# polarTRX.net
KiCad netlist of a schematic drawn in EAGLE
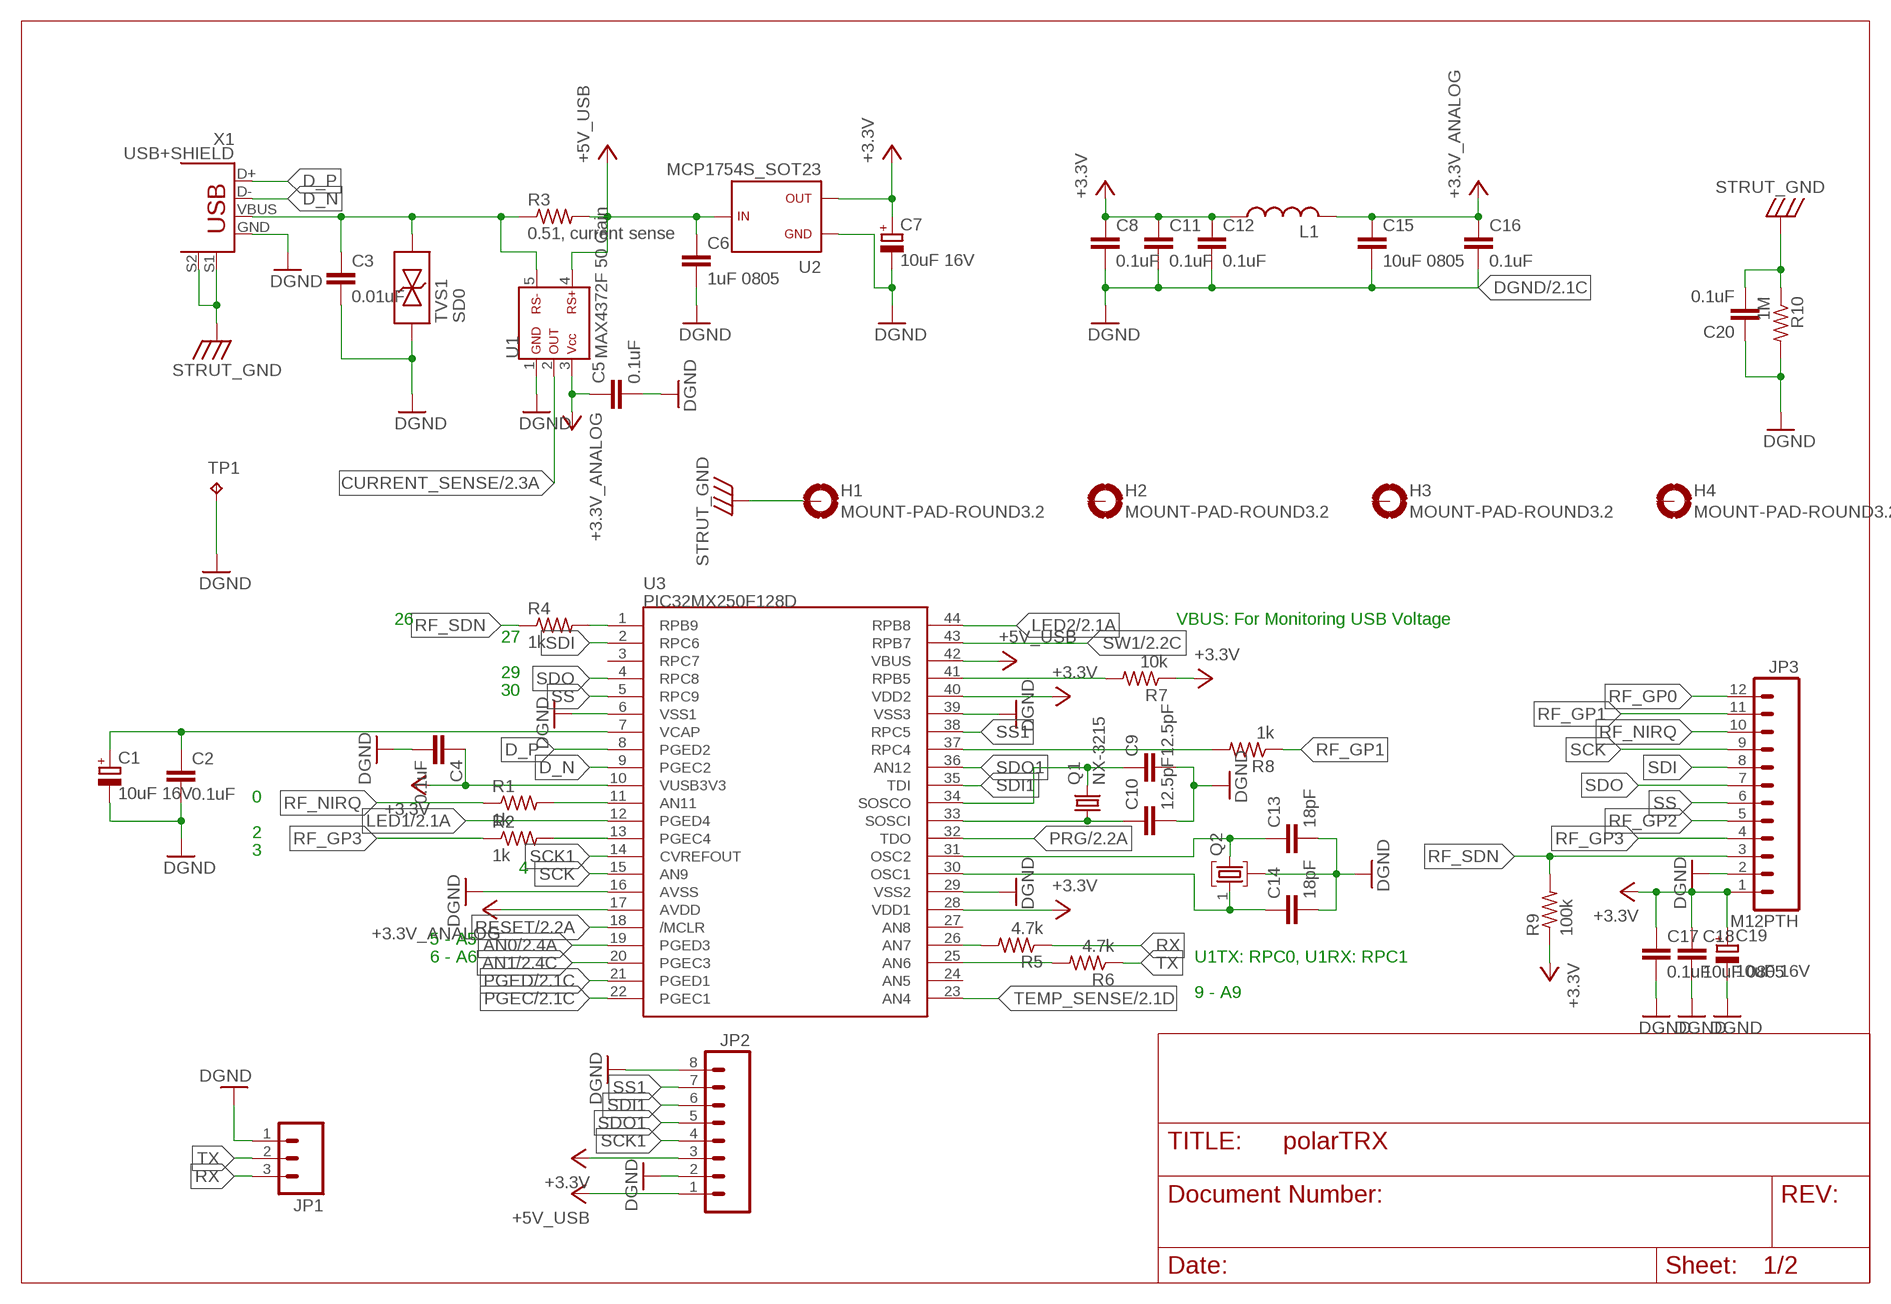
[diagram p0: schematic, sheet 1]
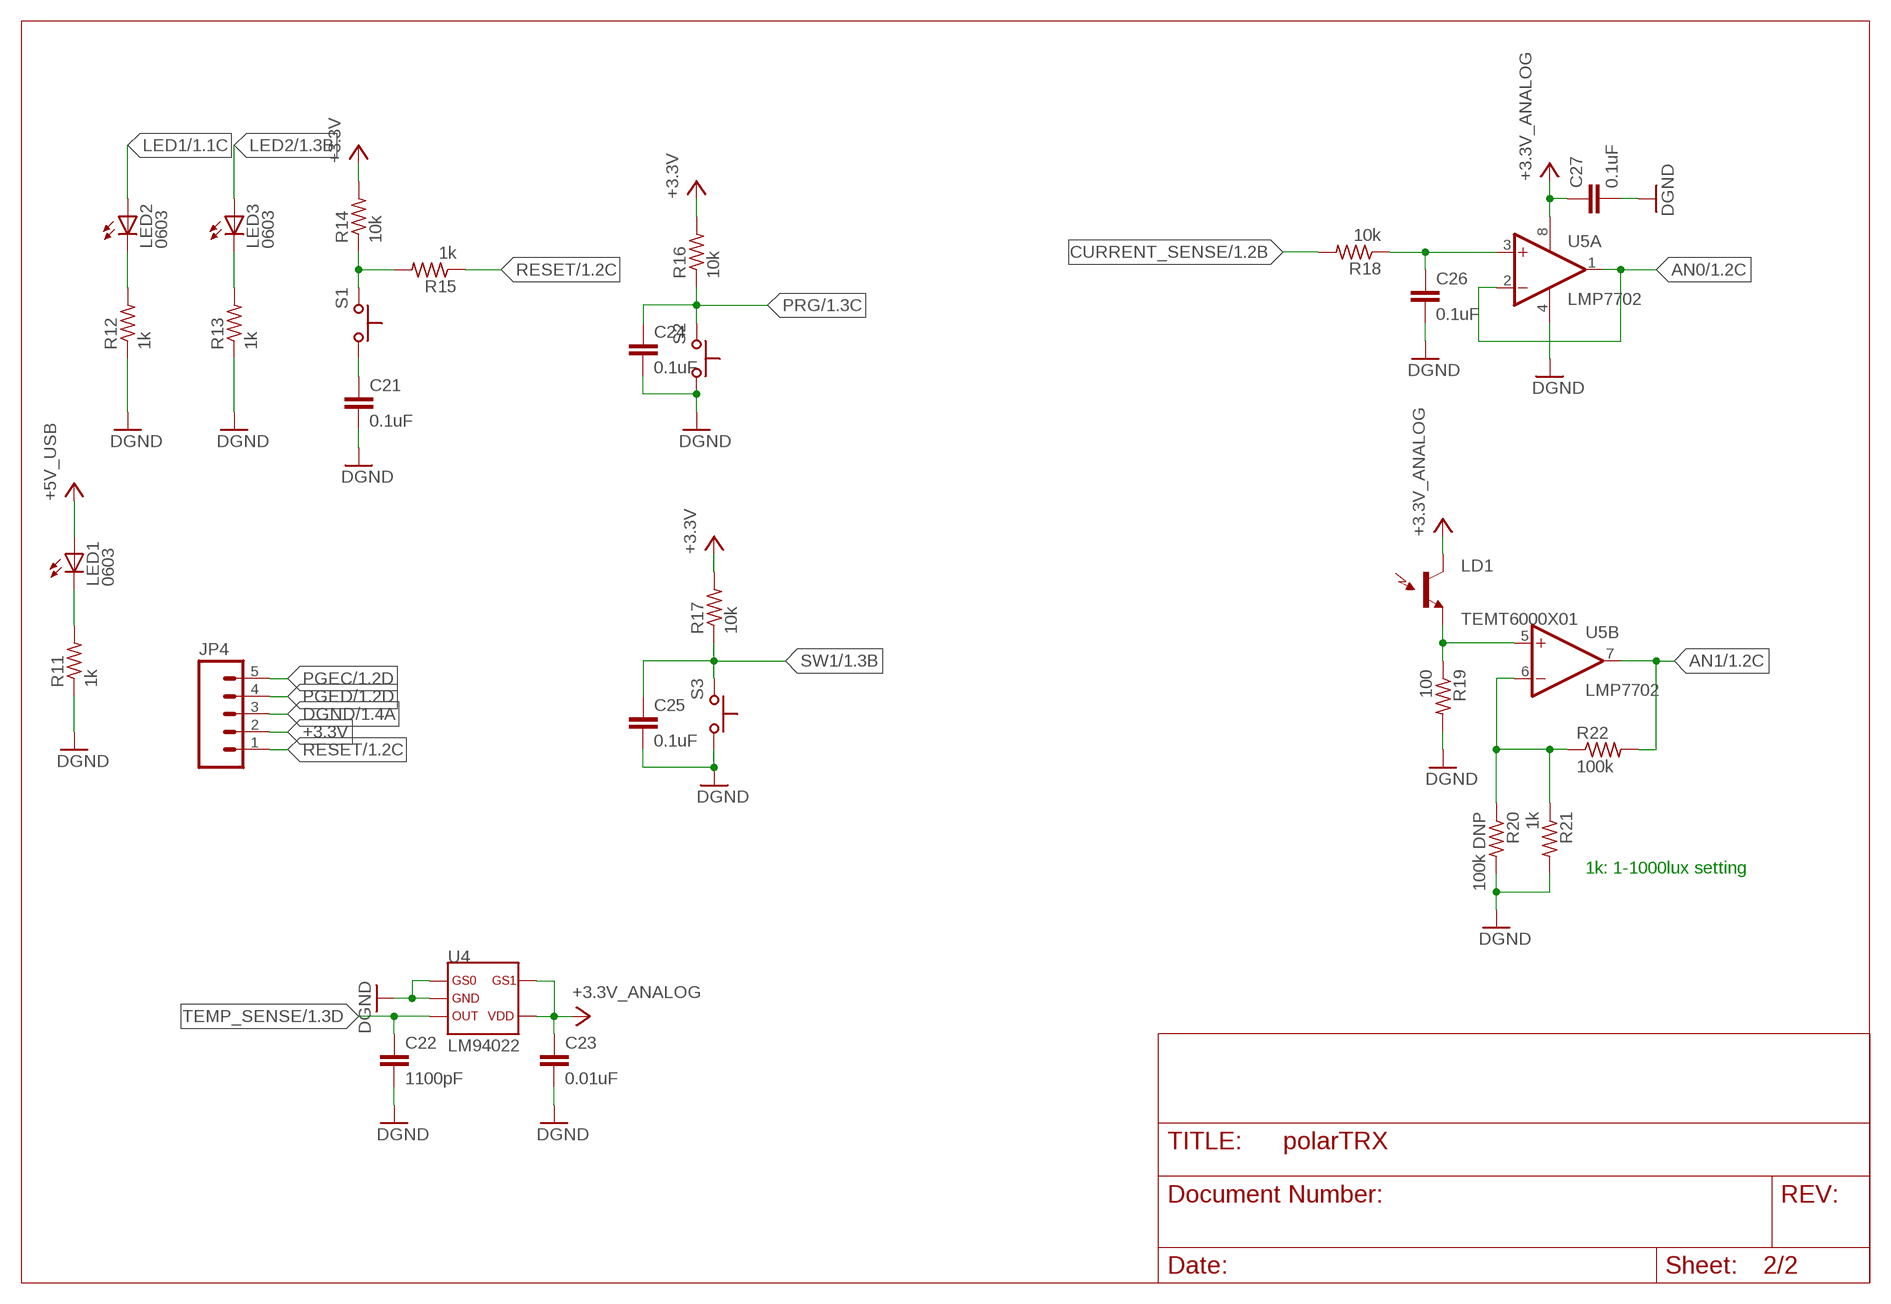
[diagram p1: schematic, sheet 2]

(export (version "E")
  (design (tool "Eeschema 10.0.6"))
  (components
    (comp (ref "C1")
      (value "10uF 16V")
      (footprint "eagle-import:C1206(3216)-A")
      (libsource (lib "eagle-import") (part "C-TANTAL-A"))
    )
    (comp (ref "C2")
      (value "0.1uF")
      (footprint "eagle-import:C0603(1608)")
      (libsource (lib "eagle-import") (part "C0603(1608)"))
    )
    (comp (ref "C3")
      (value "0.01uF")
      (footprint "eagle-import:C0603(1608)")
      (libsource (lib "eagle-import") (part "C0603(1608)"))
    )
    (comp (ref "C4")
      (value "0.1uF")
      (footprint "eagle-import:C0603(1608)")
      (libsource (lib "eagle-import") (part "C0603(1608)"))
    )
    (comp (ref "C5")
      (value "0.1uF")
      (footprint "eagle-import:C0603(1608)")
      (libsource (lib "eagle-import") (part "C0603(1608)"))
    )
    (comp (ref "C6")
      (value "1uF 0805")
      (footprint "eagle-import:C0805(2012)")
      (libsource (lib "eagle-import") (part "C0805(2012)"))
    )
    (comp (ref "C7")
      (value "10uF 16V")
      (footprint "eagle-import:C1206(3216)-A")
      (libsource (lib "eagle-import") (part "C-TANTAL-A"))
    )
    (comp (ref "C8")
      (value "0.1uF")
      (footprint "eagle-import:C0603(1608)")
      (libsource (lib "eagle-import") (part "C0603(1608)"))
    )
    (comp (ref "C9")
      (value "12.5pF")
      (footprint "eagle-import:C0603(1608)")
      (libsource (lib "eagle-import") (part "C0603(1608)"))
    )
    (comp (ref "C10")
      (value "12.5pF")
      (footprint "eagle-import:C0603(1608)")
      (libsource (lib "eagle-import") (part "C0603(1608)"))
    )
    (comp (ref "C11")
      (value "0.1uF")
      (footprint "eagle-import:C0603(1608)")
      (libsource (lib "eagle-import") (part "C0603(1608)"))
    )
    (comp (ref "C12")
      (value "0.1uF")
      (footprint "eagle-import:C0603(1608)")
      (libsource (lib "eagle-import") (part "C0603(1608)"))
    )
    (comp (ref "C13")
      (value "18pF")
      (footprint "eagle-import:C0603(1608)")
      (libsource (lib "eagle-import") (part "C0603(1608)"))
    )
    (comp (ref "C14")
      (value "18pF")
      (footprint "eagle-import:C0603(1608)")
      (libsource (lib "eagle-import") (part "C0603(1608)"))
    )
    (comp (ref "C15")
      (value "10uF 0805")
      (footprint "eagle-import:C0805(2012)")
      (libsource (lib "eagle-import") (part "C0805(2012)"))
    )
    (comp (ref "C16")
      (value "0.1uF")
      (footprint "eagle-import:C0603(1608)")
      (libsource (lib "eagle-import") (part "C0603(1608)"))
    )
    (comp (ref "C17")
      (value "0.1uF")
      (footprint "eagle-import:C0603(1608)")
      (libsource (lib "eagle-import") (part "C0603(1608)"))
    )
    (comp (ref "C18")
      (value "10uF 0805")
      (footprint "eagle-import:C0805(2012)")
      (libsource (lib "eagle-import") (part "C0805(2012)"))
    )
    (comp (ref "C19")
      (value "10uF 16V")
      (footprint "eagle-import:C1206(3216)-A")
      (libsource (lib "eagle-import") (part "C-TANTAL-A"))
    )
    (comp (ref "C20")
      (value "0.1uF")
      (footprint "eagle-import:C0603(1608)")
      (libsource (lib "eagle-import") (part "yBrainDigital_C0603(1608)"))
    )
    (comp (ref "H1")
      (value "MOUNT-PAD-ROUND3.2")
      (footprint "eagle-import:3,2-PAD")
      (libsource (lib "eagle-import") (part "MOUNT-PAD-ROUND3.2"))
    )
    (comp (ref "H2")
      (value "MOUNT-PAD-ROUND3.2")
      (footprint "eagle-import:3,2-PAD")
      (libsource (lib "eagle-import") (part "MOUNT-PAD-ROUND3.2"))
    )
    (comp (ref "H3")
      (value "MOUNT-PAD-ROUND3.2")
      (footprint "eagle-import:3,2-PAD")
      (libsource (lib "eagle-import") (part "MOUNT-PAD-ROUND3.2"))
    )
    (comp (ref "H4")
      (value "MOUNT-PAD-ROUND3.2")
      (footprint "eagle-import:3,2-PAD")
      (libsource (lib "eagle-import") (part "MOUNT-PAD-ROUND3.2"))
    )
    (comp (ref "JP1")
      (value "M03PTH")
      (footprint "eagle-import:1X03")
      (libsource (lib "eagle-import") (part "M03PTH"))
    )
    (comp (ref "JP2")
      (value "M08SILK_FEMALE_PTH")
      (footprint "eagle-import:1X08")
      (libsource (lib "eagle-import") (part "M08SILK_FEMALE_PTH"))
    )
    (comp (ref "JP3")
      (value "M12PTH")
      (footprint "eagle-import:1X12")
      (libsource (lib "eagle-import") (part "M12PTH"))
    )
    (comp (ref "L1")
      (value "L0805(2012)")
      (footprint "eagle-import:L0805(2012)")
      (libsource (lib "eagle-import") (part "L0805(2012)"))
    )
    (comp (ref "Q1")
      (value "NX-3215")
      (footprint "eagle-import:NX-3215")
      (libsource (lib "eagle-import") (part "NX-3215"))
    )
    (comp (ref "Q2")
      (value "CRYSTAL")
      (footprint "eagle-import:HC_49US")
      (libsource (lib "eagle-import") (part "CRYSTAL"))
    )
    (comp (ref "R1")
      (value "1k")
      (footprint "eagle-import:R0603(1608)")
      (libsource (lib "eagle-import") (part "R0603(1608)"))
    )
    (comp (ref "R2")
      (value "1k")
      (footprint "eagle-import:R0603(1608)")
      (libsource (lib "eagle-import") (part "R0603(1608)"))
    )
    (comp (ref "R3")
      (value "0.51, current sense")
      (footprint "eagle-import:R0805(2012)")
      (libsource (lib "eagle-import") (part "R0805(2012)"))
    )
    (comp (ref "R4")
      (value "1k")
      (footprint "eagle-import:R0603(1608)")
      (libsource (lib "eagle-import") (part "R0603(1608)"))
    )
    (comp (ref "R5")
      (value "4.7k")
      (footprint "eagle-import:R0603(1608)")
      (libsource (lib "eagle-import") (part "R0603(1608)"))
    )
    (comp (ref "R6")
      (value "4.7k")
      (footprint "eagle-import:R0603(1608)")
      (libsource (lib "eagle-import") (part "R0603(1608)"))
    )
    (comp (ref "R7")
      (value "10k")
      (footprint "eagle-import:R0603(1608)")
      (libsource (lib "eagle-import") (part "R0603(1608)"))
    )
    (comp (ref "R8")
      (value "1k")
      (footprint "eagle-import:R0603(1608)")
      (libsource (lib "eagle-import") (part "R0603(1608)"))
    )
    (comp (ref "R9")
      (value "100k")
      (footprint "eagle-import:R0603(1608)")
      (libsource (lib "eagle-import") (part "R0603(1608)"))
    )
    (comp (ref "R10")
      (value "1M")
      (footprint "eagle-import:R0603(1608)")
      (libsource (lib "eagle-import") (part "yBrainDigital_R0603(1608)"))
    )
    (comp (ref "TP1")
      (value "TP")
      (footprint "eagle-import:TP-13")
      (libsource (lib "eagle-import") (part "TP"))
    )
    (comp (ref "TVS1")
      (value "SD0")
      (footprint "eagle-import:SOD-323-NOPOL")
      (libsource (lib "eagle-import") (part "SD0"))
    )
    (comp (ref "U1")
      (value "MAX4372F 50 Gain")
      (footprint "eagle-import:SOT23-5DBV")
      (libsource (lib "eagle-import") (part "MAX4372"))
    )
    (comp (ref "U2")
      (value "MCP1754S_SOT23")
      (footprint "eagle-import:SOT23")
      (libsource (lib "eagle-import") (part "MCP1754S_SOT23"))
    )
    (comp (ref "U3")
      (value "PIC32MX250F128D")
      (footprint "eagle-import:TQFP44")
      (libsource (lib "eagle-import") (part "PIC32MX250F128D"))
    )
    (comp (ref "X1")
      (value "USB+SHIELD")
      (footprint "eagle-import:USB-B-PTH")
      (libsource (lib "eagle-import") (part "USB+SHIELD"))
    )
    (comp (ref "C21")
      (value "0.1uF")
      (footprint "eagle-import:C0603(1608)")
      (libsource (lib "eagle-import") (part "C0603(1608)"))
    )
    (comp (ref "C22")
      (value "1100pF")
      (footprint "eagle-import:C0603(1608)")
      (libsource (lib "eagle-import") (part "C0603(1608)"))
    )
    (comp (ref "C23")
      (value "0.01uF")
      (footprint "eagle-import:C0603(1608)")
      (libsource (lib "eagle-import") (part "C0603(1608)"))
    )
    (comp (ref "C24")
      (value "0.1uF")
      (footprint "eagle-import:C0603(1608)")
      (libsource (lib "eagle-import") (part "C0603(1608)"))
    )
    (comp (ref "C25")
      (value "0.1uF")
      (footprint "eagle-import:C0603(1608)")
      (libsource (lib "eagle-import") (part "C0603(1608)"))
    )
    (comp (ref "C26")
      (value "0.1uF")
      (footprint "eagle-import:C0603(1608)")
      (libsource (lib "eagle-import") (part "C0603(1608)"))
    )
    (comp (ref "C27")
      (value "0.1uF")
      (footprint "eagle-import:C0603(1608)")
      (libsource (lib "eagle-import") (part "C0603(1608)"))
    )
    (comp (ref "JP4")
      (value "M05PTH")
      (footprint "eagle-import:1X05")
      (libsource (lib "eagle-import") (part "M05PTH"))
    )
    (comp (ref "LD1")
      (value "TEMT6000X01")
      (footprint "eagle-import:TEMT6000-SEN")
      (libsource (lib "eagle-import") (part "TEMT6000X01"))
    )
    (comp (ref "LED1")
      (value "0603")
      (footprint "eagle-import:LED-0603")
      (libsource (lib "eagle-import") (part "LED0603"))
    )
    (comp (ref "LED2")
      (value "0603")
      (footprint "eagle-import:LED-0603")
      (libsource (lib "eagle-import") (part "LED0603"))
    )
    (comp (ref "LED3")
      (value "0603")
      (footprint "eagle-import:LED-0603")
      (libsource (lib "eagle-import") (part "LED0603"))
    )
    (comp (ref "R11")
      (value "1k")
      (footprint "eagle-import:R0603(1608)")
      (libsource (lib "eagle-import") (part "R0603(1608)"))
    )
    (comp (ref "R12")
      (value "1k")
      (footprint "eagle-import:R0603(1608)")
      (libsource (lib "eagle-import") (part "R0603(1608)"))
    )
    (comp (ref "R13")
      (value "1k")
      (footprint "eagle-import:R0603(1608)")
      (libsource (lib "eagle-import") (part "R0603(1608)"))
    )
    (comp (ref "R14")
      (value "10k")
      (footprint "eagle-import:R0603(1608)")
      (libsource (lib "eagle-import") (part "R0603(1608)"))
    )
    (comp (ref "R15")
      (value "1k")
      (footprint "eagle-import:R0603(1608)")
      (libsource (lib "eagle-import") (part "R0603(1608)"))
    )
    (comp (ref "R16")
      (value "10k")
      (footprint "eagle-import:R0603(1608)")
      (libsource (lib "eagle-import") (part "R0603(1608)"))
    )
    (comp (ref "R17")
      (value "10k")
      (footprint "eagle-import:R0603(1608)")
      (libsource (lib "eagle-import") (part "R0603(1608)"))
    )
    (comp (ref "R18")
      (value "10k")
      (footprint "eagle-import:R0603(1608)")
      (libsource (lib "eagle-import") (part "R0603(1608)"))
    )
    (comp (ref "R19")
      (value "100")
      (footprint "eagle-import:R0603(1608)")
      (libsource (lib "eagle-import") (part "R0603(1608)"))
    )
    (comp (ref "R20")
      (value "100k DNP")
      (footprint "eagle-import:R0603(1608)")
      (libsource (lib "eagle-import") (part "R0603(1608)"))
    )
    (comp (ref "R21")
      (value "1k")
      (footprint "eagle-import:R0603(1608)")
      (libsource (lib "eagle-import") (part "R0603(1608)"))
    )
    (comp (ref "R22")
      (value "100k")
      (footprint "eagle-import:R0603(1608)")
      (libsource (lib "eagle-import") (part "R0603(1608)"))
    )
    (comp (ref "S1")
      (value "SWITCH")
      (footprint "eagle-import:SKHLACA010")
      (libsource (lib "eagle-import") (part "SWITCH"))
    )
    (comp (ref "S2")
      (value "SWITCH")
      (footprint "eagle-import:SKHLACA010")
      (libsource (lib "eagle-import") (part "SWITCH"))
    )
    (comp (ref "S3")
      (value "SWITCH")
      (footprint "eagle-import:SKHLACA010")
      (libsource (lib "eagle-import") (part "SWITCH"))
    )
    (comp (ref "U4")
      (value "LM94022")
      (footprint "eagle-import:SC70-5")
      (libsource (lib "eagle-import") (part "LM94022"))
    )
    (comp (ref "U5")
      (value "LMP7702")
      (footprint "eagle-import:DGK_S-DPSO-G8")
      (libsource (lib "eagle-import") (part "LMP7702"))
    )
  )
  (nets
    (net (code "1") (name "+3.3V") (class "Default")
      (node (ref "C11") (pin "1") (pinfunction "1_1") (pintype "passive"))
      (node (ref "C12") (pin "1") (pinfunction "1_1") (pintype "passive"))
      (node (ref "C17") (pin "1") (pinfunction "1_1") (pintype "passive"))
      (node (ref "C18") (pin "1") (pinfunction "1_1") (pintype "passive"))
      (node (ref "C19") (pin "1") (pinfunction "+_1") (pintype "passive"))
      (node (ref "C4") (pin "1") (pinfunction "1_1") (pintype "passive"))
      (node (ref "C7") (pin "1") (pinfunction "+_1") (pintype "passive"))
      (node (ref "C8") (pin "1") (pinfunction "1_1") (pintype "passive"))
      (node (ref "JP2") (pin "3") (pinfunction "3_3") (pintype "passive"))
      (node (ref "JP3") (pin "1") (pinfunction "1_1") (pintype "passive"))
      (node (ref "JP4") (pin "2") (pinfunction "2_2") (pintype "passive"))
      (node (ref "L1") (pin "1") (pinfunction "1_1") (pintype "passive"))
      (node (ref "R14") (pin "2") (pinfunction "2_2") (pintype "passive"))
      (node (ref "R16") (pin "2") (pinfunction "2_2") (pintype "passive"))
      (node (ref "R17") (pin "2") (pinfunction "2_2") (pintype "passive"))
      (node (ref "R7") (pin "1") (pinfunction "1_1") (pintype "passive"))
      (node (ref "R9") (pin "1") (pinfunction "1_1") (pintype "passive"))
      (node (ref "U2") (pin "2") (pinfunction "2_2") (pintype "power_in"))
      (node (ref "U3") (pin "10") (pinfunction "VUSB3V3_10") (pintype "bidirectional"))
      (node (ref "U3") (pin "28") (pinfunction "VDD1_28") (pintype "bidirectional"))
      (node (ref "U3") (pin "40") (pinfunction "VDD2_40") (pintype "bidirectional"))
    )
    (net (code "2") (name "+3.3V_ANALOG") (class "Default")
      (node (ref "C15") (pin "1") (pinfunction "1_1") (pintype "passive"))
      (node (ref "C16") (pin "1") (pinfunction "1_1") (pintype "passive"))
      (node (ref "C23") (pin "1") (pinfunction "1_1") (pintype "passive"))
      (node (ref "C27") (pin "1") (pinfunction "1_1") (pintype "passive"))
      (node (ref "C5") (pin "1") (pinfunction "1_1") (pintype "passive"))
      (node (ref "L1") (pin "2") (pinfunction "2_2") (pintype "passive"))
      (node (ref "LD1") (pin "COLLECTOR") (pinfunction "C1_COLLECTOR") (pintype "passive"))
      (node (ref "U1") (pin "3") (pinfunction "P$3_3") (pintype "power_in"))
      (node (ref "U3") (pin "17") (pinfunction "AVDD_17") (pintype "bidirectional"))
      (node (ref "U4") (pin "4") (pinfunction "P$4_4") (pintype "power_in"))
      (node (ref "U4") (pin "5") (pinfunction "P$5_5") (pintype "passive"))
      (node (ref "U5") (pin "8") (pinfunction "V+_8") (pintype "power_in"))
    )
    (net (code "3") (name "+5V_USB") (class "Default")
      (node (ref "C6") (pin "1") (pinfunction "1_1") (pintype "passive"))
      (node (ref "JP2") (pin "1") (pinfunction "1_1") (pintype "passive"))
      (node (ref "LED1") (pin "A") (pinfunction "A_A") (pintype "passive"))
      (node (ref "R3") (pin "2") (pinfunction "2_2") (pintype "passive"))
      (node (ref "U1") (pin "4") (pinfunction "P$4_4") (pintype "input"))
      (node (ref "U2") (pin "3") (pinfunction "3_3") (pintype "power_in"))
      (node (ref "U3") (pin "42") (pinfunction "VBUS_42") (pintype "bidirectional"))
    )
    (net (code "4") (name "AN0") (class "Default")
      (node (ref "U3") (pin "19") (pinfunction "PGED3_19") (pintype "bidirectional"))
      (node (ref "U5") (pin "1") (pinfunction "OUT_1") (pintype "output"))
      (node (ref "U5") (pin "2") (pinfunction "-IN_2") (pintype "input"))
    )
    (net (code "5") (name "AN1") (class "Default")
      (node (ref "R22") (pin "2") (pinfunction "2_2") (pintype "passive"))
      (node (ref "U3") (pin "20") (pinfunction "PGEC3_20") (pintype "bidirectional"))
      (node (ref "U5") (pin "7") (pinfunction "OUT_7") (pintype "output"))
    )
    (net (code "6") (name "CURRENT_SENSE") (class "Default")
      (node (ref "R18") (pin "2") (pinfunction "2_2") (pintype "passive"))
      (node (ref "U1") (pin "2") (pinfunction "P$2_2") (pintype "output"))
    )
    (net (code "7") (name "DGND") (class "Default")
      (node (ref "C1") (pin "2") (pinfunction "-_2") (pintype "passive"))
      (node (ref "C10") (pin "2") (pinfunction "2_2") (pintype "passive"))
      (node (ref "C11") (pin "2") (pinfunction "2_2") (pintype "passive"))
      (node (ref "C12") (pin "2") (pinfunction "2_2") (pintype "passive"))
      (node (ref "C13") (pin "2") (pinfunction "2_2") (pintype "passive"))
      (node (ref "C14") (pin "2") (pinfunction "2_2") (pintype "passive"))
      (node (ref "C15") (pin "2") (pinfunction "2_2") (pintype "passive"))
      (node (ref "C16") (pin "2") (pinfunction "2_2") (pintype "passive"))
      (node (ref "C17") (pin "2") (pinfunction "2_2") (pintype "passive"))
      (node (ref "C18") (pin "2") (pinfunction "2_2") (pintype "passive"))
      (node (ref "C19") (pin "2") (pinfunction "-_2") (pintype "passive"))
      (node (ref "C2") (pin "2") (pinfunction "2_2") (pintype "passive"))
      (node (ref "C20") (pin "1") (pinfunction "1_1") (pintype "passive"))
      (node (ref "C21") (pin "2") (pinfunction "2_2") (pintype "passive"))
      (node (ref "C22") (pin "2") (pinfunction "2_2") (pintype "passive"))
      (node (ref "C23") (pin "2") (pinfunction "2_2") (pintype "passive"))
      (node (ref "C24") (pin "2") (pinfunction "2_2") (pintype "passive"))
      (node (ref "C25") (pin "2") (pinfunction "2_2") (pintype "passive"))
      (node (ref "C26") (pin "2") (pinfunction "2_2") (pintype "passive"))
      (node (ref "C27") (pin "2") (pinfunction "2_2") (pintype "passive"))
      (node (ref "C3") (pin "2") (pinfunction "2_2") (pintype "passive"))
      (node (ref "C4") (pin "2") (pinfunction "2_2") (pintype "passive"))
      (node (ref "C5") (pin "2") (pinfunction "2_2") (pintype "passive"))
      (node (ref "C6") (pin "2") (pinfunction "2_2") (pintype "passive"))
      (node (ref "C7") (pin "2") (pinfunction "-_2") (pintype "passive"))
      (node (ref "C8") (pin "2") (pinfunction "2_2") (pintype "passive"))
      (node (ref "C9") (pin "2") (pinfunction "2_2") (pintype "passive"))
      (node (ref "JP1") (pin "1") (pinfunction "1_1") (pintype "passive"))
      (node (ref "JP2") (pin "2") (pinfunction "2_2") (pintype "passive"))
      (node (ref "JP2") (pin "8") (pinfunction "8_8") (pintype "passive"))
      (node (ref "JP3") (pin "2") (pinfunction "2_2") (pintype "passive"))
      (node (ref "JP4") (pin "3") (pinfunction "3_3") (pintype "passive"))
      (node (ref "Q2") (pin "2") (pinfunction "2_2") (pintype "passive"))
      (node (ref "R10") (pin "2") (pinfunction "2_2") (pintype "passive"))
      (node (ref "R11") (pin "1") (pinfunction "1_1") (pintype "passive"))
      (node (ref "R12") (pin "1") (pinfunction "1_1") (pintype "passive"))
      (node (ref "R13") (pin "1") (pinfunction "1_1") (pintype "passive"))
      (node (ref "R19") (pin "2") (pinfunction "2_2") (pintype "passive"))
      (node (ref "R20") (pin "2") (pinfunction "2_2") (pintype "passive"))
      (node (ref "R21") (pin "2") (pinfunction "2_2") (pintype "passive"))
      (node (ref "S2") (pin "P$2") (pinfunction "P$2_P$2") (pintype "bidirectional"))
      (node (ref "S3") (pin "P$2") (pinfunction "P$2_P$2") (pintype "bidirectional"))
      (node (ref "TP1") (pin "TP") (pinfunction "TP_TP") (pintype "input"))
      (node (ref "TVS1") (pin "1") (pinfunction "P$1_1") (pintype "bidirectional"))
      (node (ref "U1") (pin "1") (pinfunction "P$1_1") (pintype "power_in"))
      (node (ref "U2") (pin "1") (pinfunction "1_1") (pintype "power_in"))
      (node (ref "U3") (pin "16") (pinfunction "AVSS_16") (pintype "bidirectional"))
      (node (ref "U3") (pin "29") (pinfunction "VSS2_29") (pintype "bidirectional"))
      (node (ref "U3") (pin "39") (pinfunction "VSS3_39") (pintype "bidirectional"))
      (node (ref "U3") (pin "6") (pinfunction "VSS1_6") (pintype "bidirectional"))
      (node (ref "U4") (pin "1") (pinfunction "P$1_1") (pintype "passive"))
      (node (ref "U4") (pin "2") (pinfunction "P$2_2") (pintype "power_in"))
      (node (ref "U5") (pin "4") (pinfunction "V-_4") (pintype "power_in"))
      (node (ref "X1") (pin "GND") (pinfunction "GND_GND") (pintype "bidirectional"))
    )
    (net (code "8") (name "D_N") (class "Default")
      (node (ref "U3") (pin "9") (pinfunction "PGEC2_9") (pintype "bidirectional"))
      (node (ref "X1") (pin "D-") (pinfunction "D-_D-") (pintype "bidirectional"))
    )
    (net (code "9") (name "D_P") (class "Default")
      (node (ref "U3") (pin "8") (pinfunction "PGED2_8") (pintype "bidirectional"))
      (node (ref "X1") (pin "D+") (pinfunction "D+_D+") (pintype "bidirectional"))
    )
    (net (code "10") (name "LED1") (class "Default")
      (node (ref "LED2") (pin "A") (pinfunction "A_A") (pintype "passive"))
      (node (ref "U3") (pin "12") (pinfunction "PGED4_12") (pintype "bidirectional"))
    )
    (net (code "11") (name "LED2") (class "Default")
      (node (ref "LED3") (pin "A") (pinfunction "A_A") (pintype "passive"))
      (node (ref "U3") (pin "44") (pinfunction "RPB8_44") (pintype "bidirectional"))
    )
    (net (code "12") (name "Net-(C1-+)") (class "Default")
      (node (ref "C1") (pin "1") (pinfunction "+_1") (pintype "passive"))
      (node (ref "C2") (pin "1") (pinfunction "1_1") (pintype "passive"))
      (node (ref "U3") (pin "7") (pinfunction "VCAP_7") (pintype "bidirectional"))
    )
    (net (code "13") (name "Net-(C21-Pad1)") (class "Default")
      (node (ref "C21") (pin "1") (pinfunction "1_1") (pintype "passive"))
      (node (ref "S1") (pin "P$2") (pinfunction "P$2_P$2") (pintype "bidirectional"))
    )
    (net (code "14") (name "Net-(LD1-E1)") (class "Default")
      (node (ref "LD1") (pin "EMITTER") (pinfunction "E1_EMITTER") (pintype "passive"))
      (node (ref "R19") (pin "1") (pinfunction "1_1") (pintype "passive"))
      (node (ref "U5") (pin "5") (pinfunction "+IN_5") (pintype "input"))
    )
    (net (code "15") (name "Net-(LED1-PadC)") (class "Default")
      (node (ref "LED1") (pin "C") (pinfunction "C_C") (pintype "passive"))
      (node (ref "R11") (pin "2") (pinfunction "2_2") (pintype "passive"))
    )
    (net (code "16") (name "Net-(LED2-PadC)") (class "Default")
      (node (ref "LED2") (pin "C") (pinfunction "C_C") (pintype "passive"))
      (node (ref "R12") (pin "2") (pinfunction "2_2") (pintype "passive"))
    )
    (net (code "17") (name "Net-(LED3-PadC)") (class "Default")
      (node (ref "LED3") (pin "C") (pinfunction "C_C") (pintype "passive"))
      (node (ref "R13") (pin "2") (pinfunction "2_2") (pintype "passive"))
    )
    (net (code "18") (name "Net-(R14-Pad1)") (class "Default")
      (node (ref "R14") (pin "1") (pinfunction "1_1") (pintype "passive"))
      (node (ref "R15") (pin "2") (pinfunction "2_2") (pintype "passive"))
      (node (ref "S1") (pin "P$1") (pinfunction "P$1_P$1") (pintype "bidirectional"))
    )
    (net (code "19") (name "Net-(TVS1-P$2)") (class "Default")
      (node (ref "C3") (pin "1") (pinfunction "1_1") (pintype "passive"))
      (node (ref "R3") (pin "1") (pinfunction "1_1") (pintype "passive"))
      (node (ref "TVS1") (pin "2") (pinfunction "P$2_2") (pintype "bidirectional"))
      (node (ref "U1") (pin "5") (pinfunction "P$5_5") (pintype "input"))
      (node (ref "X1") (pin "VBUS") (pinfunction "VBUS_VBUS") (pintype "bidirectional"))
    )
    (net (code "20") (name "Net-(U3-AN6)") (class "Default")
      (node (ref "R6") (pin "2") (pinfunction "2_2") (pintype "passive"))
      (node (ref "U3") (pin "25") (pinfunction "AN6_25") (pintype "bidirectional"))
    )
    (net (code "21") (name "Net-(U3-AN7)") (class "Default")
      (node (ref "R5") (pin "2") (pinfunction "2_2") (pintype "passive"))
      (node (ref "U3") (pin "26") (pinfunction "AN7_26") (pintype "bidirectional"))
    )
    (net (code "22") (name "Net-(U3-AN11)") (class "Default")
      (node (ref "R1") (pin "2") (pinfunction "2_2") (pintype "passive"))
      (node (ref "U3") (pin "11") (pinfunction "AN11_11") (pintype "bidirectional"))
    )
    (net (code "23") (name "Net-(U3-OSC1)") (class "Default")
      (node (ref "C14") (pin "1") (pinfunction "1_1") (pintype "passive"))
      (node (ref "Q2") (pin "1") (pinfunction "1_1") (pintype "passive"))
      (node (ref "U3") (pin "30") (pinfunction "OSC1_30") (pintype "bidirectional"))
    )
    (net (code "24") (name "Net-(U3-OSC2)") (class "Default")
      (node (ref "C13") (pin "1") (pinfunction "1_1") (pintype "passive"))
      (node (ref "Q2") (pin "3") (pinfunction "3_3") (pintype "passive"))
      (node (ref "U3") (pin "31") (pinfunction "OSC2_31") (pintype "bidirectional"))
    )
    (net (code "25") (name "Net-(U3-PGEC4)") (class "Default")
      (node (ref "R2") (pin "2") (pinfunction "2_2") (pintype "passive"))
      (node (ref "U3") (pin "13") (pinfunction "PGEC4_13") (pintype "bidirectional"))
    )
    (net (code "26") (name "Net-(U3-RPB5)") (class "Default")
      (node (ref "R7") (pin "2") (pinfunction "2_2") (pintype "passive"))
      (node (ref "U3") (pin "41") (pinfunction "RPB5_41") (pintype "bidirectional"))
    )
    (net (code "27") (name "Net-(U3-RPB9)") (class "Default")
      (node (ref "R4") (pin "2") (pinfunction "2_2") (pintype "passive"))
      (node (ref "U3") (pin "1") (pinfunction "RPB9_1") (pintype "bidirectional"))
    )
    (net (code "28") (name "Net-(U3-RPC4)") (class "Default")
      (node (ref "R8") (pin "2") (pinfunction "2_2") (pintype "passive"))
      (node (ref "U3") (pin "37") (pinfunction "RPC4_37") (pintype "bidirectional"))
    )
    (net (code "29") (name "Net-(U3-SOSCI)") (class "Default")
      (node (ref "C10") (pin "1") (pinfunction "1_1") (pintype "passive"))
      (node (ref "Q1") (pin "1") (pinfunction "1_1") (pintype "passive"))
      (node (ref "U3") (pin "33") (pinfunction "SOSCI_33") (pintype "bidirectional"))
    )
    (net (code "30") (name "Net-(U3-SOSCO)") (class "Default")
      (node (ref "C9") (pin "1") (pinfunction "1_1") (pintype "passive"))
      (node (ref "Q1") (pin "2") (pinfunction "2_2") (pintype "passive"))
      (node (ref "U3") (pin "34") (pinfunction "SOSCO_34") (pintype "bidirectional"))
    )
    (net (code "31") (name "Net-(U5A-+IN)") (class "Default")
      (node (ref "C26") (pin "1") (pinfunction "1_1") (pintype "passive"))
      (node (ref "R18") (pin "1") (pinfunction "1_1") (pintype "passive"))
      (node (ref "U5") (pin "3") (pinfunction "+IN_3") (pintype "input"))
    )
    (net (code "32") (name "Net-(U5B--IN)") (class "Default")
      (node (ref "R20") (pin "1") (pinfunction "1_1") (pintype "passive"))
      (node (ref "R21") (pin "1") (pinfunction "1_1") (pintype "passive"))
      (node (ref "R22") (pin "1") (pinfunction "1_1") (pintype "passive"))
      (node (ref "U5") (pin "6") (pinfunction "-IN_6") (pintype "input"))
    )
    (net (code "33") (name "PGEC") (class "Default")
      (node (ref "JP4") (pin "5") (pinfunction "5_5") (pintype "passive"))
      (node (ref "U3") (pin "22") (pinfunction "PGEC1_22") (pintype "bidirectional"))
    )
    (net (code "34") (name "PGED") (class "Default")
      (node (ref "JP4") (pin "4") (pinfunction "4_4") (pintype "passive"))
      (node (ref "U3") (pin "21") (pinfunction "PGED1_21") (pintype "bidirectional"))
    )
    (net (code "35") (name "PRG") (class "Default")
      (node (ref "C24") (pin "1") (pinfunction "1_1") (pintype "passive"))
      (node (ref "R16") (pin "1") (pinfunction "1_1") (pintype "passive"))
      (node (ref "S2") (pin "P$1") (pinfunction "P$1_P$1") (pintype "bidirectional"))
      (node (ref "U3") (pin "32") (pinfunction "TDO_32") (pintype "bidirectional"))
    )
    (net (code "36") (name "RESET") (class "Default")
      (node (ref "JP4") (pin "1") (pinfunction "1_1") (pintype "passive"))
      (node (ref "R15") (pin "1") (pinfunction "1_1") (pintype "passive"))
      (node (ref "U3") (pin "18") (pinfunction "/MCLR_18") (pintype "bidirectional"))
    )
    (net (code "37") (name "RF_GP0") (class "Default")
      (node (ref "JP3") (pin "12") (pinfunction "12_12") (pintype "passive"))
    )
    (net (code "38") (name "RF_GP1") (class "Default")
      (node (ref "JP3") (pin "11") (pinfunction "11_11") (pintype "passive"))
      (node (ref "R8") (pin "1") (pinfunction "1_1") (pintype "passive"))
    )
    (net (code "39") (name "RF_GP2") (class "Default")
      (node (ref "JP3") (pin "5") (pinfunction "5_5") (pintype "passive"))
    )
    (net (code "40") (name "RF_GP3") (class "Default")
      (node (ref "JP3") (pin "4") (pinfunction "4_4") (pintype "passive"))
      (node (ref "R2") (pin "1") (pinfunction "1_1") (pintype "passive"))
    )
    (net (code "41") (name "RF_NIRQ") (class "Default")
      (node (ref "JP3") (pin "10") (pinfunction "10_10") (pintype "passive"))
      (node (ref "R1") (pin "1") (pinfunction "1_1") (pintype "passive"))
    )
    (net (code "42") (name "RF_SDN") (class "Default")
      (node (ref "JP3") (pin "3") (pinfunction "3_3") (pintype "passive"))
      (node (ref "R4") (pin "1") (pinfunction "1_1") (pintype "passive"))
      (node (ref "R9") (pin "2") (pinfunction "2_2") (pintype "passive"))
    )
    (net (code "43") (name "RX") (class "Default")
      (node (ref "JP1") (pin "3") (pinfunction "3_3") (pintype "passive"))
      (node (ref "R5") (pin "1") (pinfunction "1_1") (pintype "passive"))
    )
    (net (code "44") (name "SCK") (class "Default")
      (node (ref "JP3") (pin "9") (pinfunction "9_9") (pintype "passive"))
      (node (ref "U3") (pin "15") (pinfunction "AN9_15") (pintype "bidirectional"))
    )
    (net (code "45") (name "SCK1") (class "Default")
      (node (ref "JP2") (pin "4") (pinfunction "4_4") (pintype "passive"))
      (node (ref "U3") (pin "14") (pinfunction "CVREFOUT_14") (pintype "bidirectional"))
    )
    (net (code "46") (name "SDI") (class "Default")
      (node (ref "JP3") (pin "8") (pinfunction "8_8") (pintype "passive"))
      (node (ref "U3") (pin "2") (pinfunction "RPC6_2") (pintype "bidirectional"))
    )
    (net (code "47") (name "SDI1") (class "Default")
      (node (ref "JP2") (pin "6") (pinfunction "6_6") (pintype "passive"))
      (node (ref "U3") (pin "35") (pinfunction "TDI_35") (pintype "bidirectional"))
    )
    (net (code "48") (name "SDO") (class "Default")
      (node (ref "JP3") (pin "7") (pinfunction "7_7") (pintype "passive"))
      (node (ref "U3") (pin "4") (pinfunction "RPC8_4") (pintype "bidirectional"))
    )
    (net (code "49") (name "SDO1") (class "Default")
      (node (ref "JP2") (pin "5") (pinfunction "5_5") (pintype "passive"))
      (node (ref "U3") (pin "36") (pinfunction "AN12_36") (pintype "bidirectional"))
    )
    (net (code "50") (name "SS") (class "Default")
      (node (ref "JP3") (pin "6") (pinfunction "6_6") (pintype "passive"))
      (node (ref "U3") (pin "5") (pinfunction "RPC9_5") (pintype "bidirectional"))
    )
    (net (code "51") (name "SS1") (class "Default")
      (node (ref "JP2") (pin "7") (pinfunction "7_7") (pintype "passive"))
      (node (ref "U3") (pin "38") (pinfunction "RPC5_38") (pintype "bidirectional"))
    )
    (net (code "52") (name "STRUT_GND") (class "Default")
      (node (ref "C20") (pin "2") (pinfunction "2_2") (pintype "passive"))
      (node (ref "H1") (pin "B3,2") (pinfunction "MOUNT_B3,2") (pintype "passive"))
      (node (ref "R10") (pin "1") (pinfunction "1_1") (pintype "passive"))
      (node (ref "X1") (pin "S1") (pinfunction "S1_S1") (pintype "bidirectional"))
      (node (ref "X1") (pin "S2") (pinfunction "S2_S2") (pintype "bidirectional"))
    )
    (net (code "53") (name "SW1") (class "Default")
      (node (ref "C25") (pin "1") (pinfunction "1_1") (pintype "passive"))
      (node (ref "R17") (pin "1") (pinfunction "1_1") (pintype "passive"))
      (node (ref "S3") (pin "P$1") (pinfunction "P$1_P$1") (pintype "bidirectional"))
      (node (ref "U3") (pin "43") (pinfunction "RPB7_43") (pintype "bidirectional"))
    )
    (net (code "54") (name "TEMP_SENSE") (class "Default")
      (node (ref "C22") (pin "1") (pinfunction "1_1") (pintype "passive"))
      (node (ref "U3") (pin "23") (pinfunction "AN4_23") (pintype "bidirectional"))
      (node (ref "U4") (pin "3") (pinfunction "P$3_3") (pintype "output"))
    )
    (net (code "55") (name "TX") (class "Default")
      (node (ref "JP1") (pin "2") (pinfunction "2_2") (pintype "passive"))
      (node (ref "R6") (pin "1") (pinfunction "1_1") (pintype "passive"))
    )
    (net (code "56") (name "unconnected-(H2-MOUNT-PadB3,2)") (class "Default")
      (node (ref "H2") (pin "B3,2") (pinfunction "MOUNT_B3,2") (pintype "passive"))
    )
    (net (code "57") (name "unconnected-(H3-MOUNT-PadB3,2)") (class "Default")
      (node (ref "H3") (pin "B3,2") (pinfunction "MOUNT_B3,2") (pintype "passive"))
    )
    (net (code "58") (name "unconnected-(H4-MOUNT-PadB3,2)") (class "Default")
      (node (ref "H4") (pin "B3,2") (pinfunction "MOUNT_B3,2") (pintype "passive"))
    )
    (net (code "59") (name "unconnected-(U3-AN5-Pad24)") (class "Default")
      (node (ref "U3") (pin "24") (pinfunction "AN5_24") (pintype "bidirectional"))
    )
    (net (code "60") (name "unconnected-(U3-AN8-Pad27)") (class "Default")
      (node (ref "U3") (pin "27") (pinfunction "AN8_27") (pintype "bidirectional"))
    )
    (net (code "61") (name "unconnected-(U3-RPC7-Pad3)") (class "Default")
      (node (ref "U3") (pin "3") (pinfunction "RPC7_3") (pintype "bidirectional"))
    )
  )
)
